# SIT1533_Oscillator.net
KiCad netlist of a schematic drawn in Altium Designer
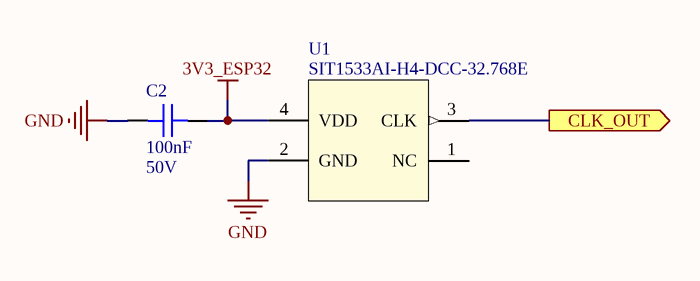
[diagram p0: SIT1533_Oscillator.SchDoc]

(export (version "E")
  (design (tool "Eeschema 10.0.6"))
  (components
    (comp (ref "C2")
      (value "CAP CER 0.1UF 50V X7R 0402")
      (footprint "C0402")
      (description "0.1µF ±10% 50V Ceramic Capacitor X7R 0402 (1005 Metric)")
      (fields
        (field (name "MANUFACTURER") "TDK")
        (field (name "MANUFACTURER PART NUMBER") "CGA2B3X7R1H104K050BB")
        (field (name "CAPACITANCE") "100nF")
        (field (name "VOLTAGE") "50V")
      )
      (libsource (lib "capacitors_smd") (part "CAP CER 0.1UF 50V X7R 0402"))
    )
    (comp (ref "U1")
      (value "IC SIT1533AI-H4-DCC-32.768E MEMS OSC XO 32.7680KHZ LVCMOS")
      (footprint "XTAL4_SiT1533_SIT")
      (description "32.768kHz XO (Standard) LVCMOS Oscillator 1.5V ~ 3.63V  4-SMD, No Lead")
      (fields
        (field (name "MANUFACTURER") "SiTime")
        (field (name "MANUFACTURER PART NUMBER") "SIT1533AI-H4-DCC-32.768E")
      )
      (libsource (lib "BLDC_Motor_Driver") (part "IC SIT1533AI-H4-DCC-32.768E MEMS OSC XO 32.7680KHZ LVCMOS"))
    )
  )
  (nets
    (net (code "1") (name "/CLK_OUT") (class "Default")
      (node (ref "U1") (pin "3") (pinfunction "CLK_3") (pintype "output"))
    )
    (net (code "2") (name "3V3_ESP32") (class "Default")
      (node (ref "C2") (pin "2") (pinfunction "2_2") (pintype "passive"))
      (node (ref "U1") (pin "4") (pinfunction "VDD_4") (pintype "power_in"))
    )
    (net (code "3") (name "GND") (class "Default")
      (node (ref "C2") (pin "1") (pinfunction "1_1") (pintype "passive"))
      (node (ref "U1") (pin "2") (pinfunction "GND_2") (pintype "power_in"))
    )
    (net (code "4") (name "unconnected-(U1-NC-Pad1)") (class "Default")
      (node (ref "U1") (pin "1") (pinfunction "NC_1") (pintype "passive"))
    )
  )
)
